# BMS.net
KiCad netlist of a schematic drawn in Altium Designer
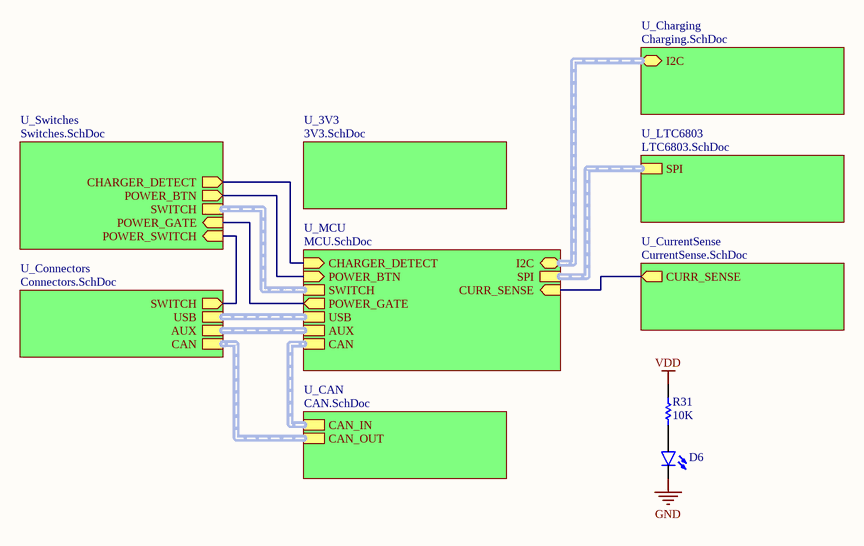
[diagram p0: BMS.SchDoc]

(export (version "E")
  (design (tool "Eeschema 10.0.6"))
  (components
    (comp (ref "D6")
      (value "LED-BLUE")
      (footprint "LED0603")
      (fields (field (name "PARTNUMBER") "LTST-C193TBKT-5A") (field (name "MANUFACTURER") "Lite-On Inc."))
      (libsource (lib "LEDs") (part "LED_0603"))
    )
    (comp (ref "R31")
      (value "10K")
      (footprint "R0603[1608]")
      (description "10K 0.25W 5% 0603 (1005 Metric)")
      (fields (field (name "TOLERANCE") "5%") (field (name "POWER") "0.25W"))
      (libsource (lib "Resistors") (part "RES_10K_0603_5%"))
    )
  )
  (nets
    (net (code "13") (name "GND") (class "Default")
      (node (ref "D6") (pin "C") (pinfunction "C_C") (pintype "passive"))
    )
    (net (code "14") (name "Net-(D6-PadA)") (class "Default")
      (node (ref "D6") (pin "A") (pinfunction "A_A") (pintype "passive"))
      (node (ref "R31") (pin "1") (pinfunction "1_1") (pintype "passive"))
    )
    (net (code "15") (name "VDD") (class "Default")
      (node (ref "R31") (pin "2") (pinfunction "2_2") (pintype "passive"))
    )
  )
)
